# I2C.net
KiCad netlist of a schematic drawn in Altium Designer
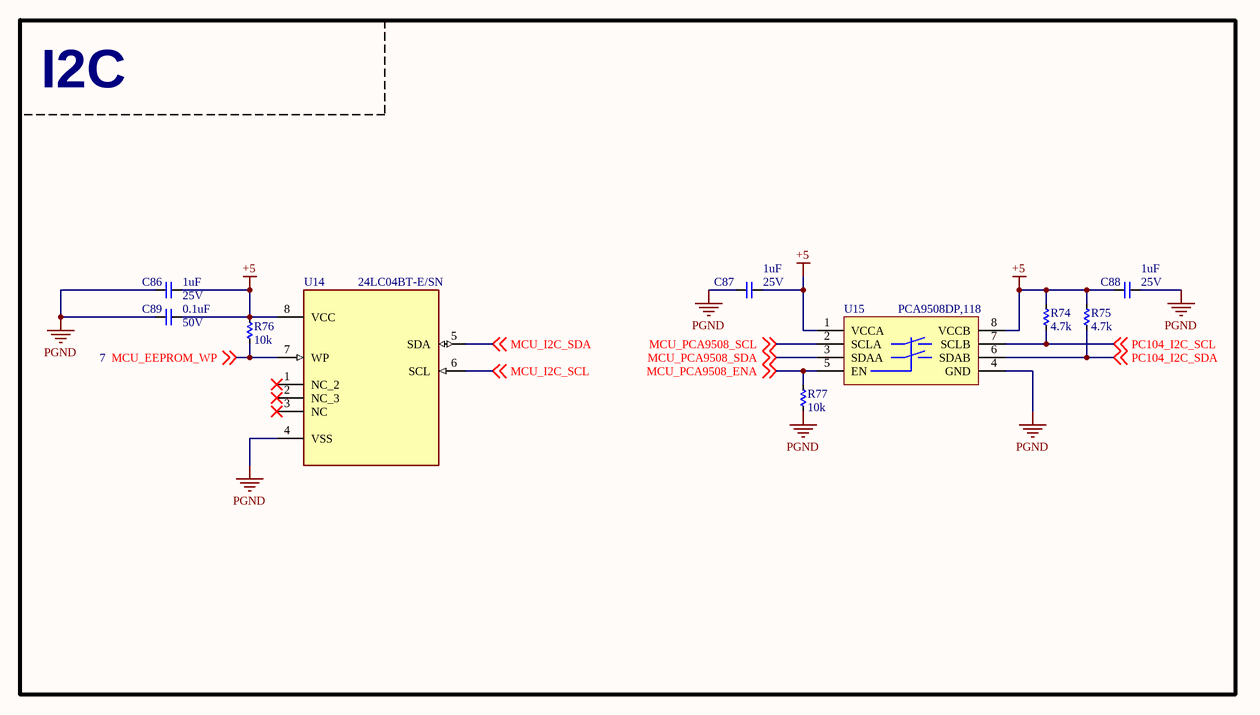
[diagram p0: I2C.SchDoc]

(export (version "E")
  (design (tool "Eeschema 10.0.6"))
  (components
    (comp (ref "C86")
      (value "1uF")
      (footprint "CAP_C_1608X80")
      (description "CAP")
      (fields (field (name "VOLTAGE") "25V"))
      (libsource (lib "LABLIB") (part "_CAP_C_2"))
    )
    (comp (ref "C87")
      (value "1uF")
      (footprint "CAP_C_1608X80")
      (description "CAP")
      (fields (field (name "VOLTAGE") "25V"))
      (libsource (lib "LABLIB") (part "_CAP_C_2"))
    )
    (comp (ref "C88")
      (value "1uF")
      (footprint "CAP_C_1608X80")
      (description "CAP")
      (fields (field (name "VOLTAGE") "25V"))
      (libsource (lib "LABLIB") (part "_CAP_C_2"))
    )
    (comp (ref "C89")
      (value "0.1uF")
      (footprint "CAP_C_1608X80")
      (description "CAP")
      (fields (field (name "VOLTAGE") "50V"))
      (libsource (lib "LABLIB") (part "_CAP_C_2"))
    )
    (comp (ref "R74")
      (value "4.7k")
      (footprint "RES_C_1608X60")
      (description "RES")
      (libsource (lib "LABLIB") (part "_RES_B_2_2"))
    )
    (comp (ref "R75")
      (value "4.7k")
      (footprint "RES_C_1608X60")
      (description "RES")
      (libsource (lib "LABLIB") (part "_RES_B_2_2"))
    )
    (comp (ref "R76")
      (value "10k")
      (footprint "RES_C_1608X60")
      (description "RES")
      (libsource (lib "LABLIB") (part "_RES_B_2_2"))
    )
    (comp (ref "R77")
      (value "10k")
      (footprint "RES_C_1608X60")
      (description "RES")
      (libsource (lib "LABLIB") (part "_RES_B_2_2"))
    )
    (comp (ref "U14")
      (value "24LC04BT-E/SN")
      (footprint "SOIC_127")
      (libsource (lib "KIENASIY123_LIB") (part "24LC04BT-E/SN"))
    )
    (comp (ref "U15")
      (value "PCA9508DP,118")
      (footprint "TSOP8")
      (libsource (lib "EXP_HW_V3") (part "PCA9508DP,118"))
    )
  )
  (nets
    (net (code "1") (name "+5") (class "Default")
      (node (ref "C86") (pin "1") (pinfunction "1_1") (pintype "passive"))
      (node (ref "C87") (pin "2") (pinfunction "2_2") (pintype "passive"))
      (node (ref "C88") (pin "2") (pinfunction "2_2") (pintype "passive"))
      (node (ref "C89") (pin "1") (pinfunction "1_1") (pintype "passive"))
      (node (ref "R74") (pin "1") (pinfunction "1_1") (pintype "passive"))
      (node (ref "R75") (pin "1") (pinfunction "1_1") (pintype "passive"))
      (node (ref "R76") (pin "1") (pinfunction "1_1") (pintype "passive"))
      (node (ref "U14") (pin "8") (pinfunction "VCC_8") (pintype "power_in"))
      (node (ref "U15") (pin "1") (pinfunction "VCCA_1") (pintype "passive"))
      (node (ref "U15") (pin "8") (pinfunction "VCCB_8") (pintype "passive"))
    )
    (net (code "2") (name "MCU_EEPROM_WP") (class "Default")
      (node (ref "R76") (pin "2") (pinfunction "2_2") (pintype "passive"))
      (node (ref "U14") (pin "7") (pinfunction "WP_7") (pintype "input"))
    )
    (net (code "3") (name "MCU_I2C_SCL") (class "Default")
      (node (ref "U14") (pin "6") (pinfunction "SCL_6") (pintype "input"))
    )
    (net (code "4") (name "MCU_I2C_SDA") (class "Default")
      (node (ref "U14") (pin "5") (pinfunction "SDA_5") (pintype "bidirectional"))
    )
    (net (code "5") (name "MCU_PCA9508_ENA") (class "Default")
      (node (ref "R77") (pin "2") (pinfunction "2_2") (pintype "passive"))
      (node (ref "U15") (pin "5") (pinfunction "EN_5") (pintype "passive"))
    )
    (net (code "6") (name "MCU_PCA9508_SCL") (class "Default")
      (node (ref "U15") (pin "2") (pinfunction "SCLA_2") (pintype "passive"))
    )
    (net (code "7") (name "MCU_PCA9508_SDA") (class "Default")
      (node (ref "U15") (pin "3") (pinfunction "SDAA_3") (pintype "passive"))
    )
    (net (code "8") (name "PC104_I2C_SCL") (class "Default")
      (node (ref "R74") (pin "2") (pinfunction "2_2") (pintype "passive"))
      (node (ref "U15") (pin "7") (pinfunction "SCLB_7") (pintype "passive"))
    )
    (net (code "9") (name "PC104_I2C_SDA") (class "Default")
      (node (ref "R75") (pin "2") (pinfunction "2_2") (pintype "passive"))
      (node (ref "U15") (pin "6") (pinfunction "SDAB_6") (pintype "passive"))
    )
    (net (code "10") (name "PGND") (class "Default")
      (node (ref "C86") (pin "2") (pinfunction "2_2") (pintype "passive"))
      (node (ref "C87") (pin "1") (pinfunction "1_1") (pintype "passive"))
      (node (ref "C88") (pin "1") (pinfunction "1_1") (pintype "passive"))
      (node (ref "C89") (pin "2") (pinfunction "2_2") (pintype "passive"))
      (node (ref "R77") (pin "1") (pinfunction "1_1") (pintype "passive"))
      (node (ref "U14") (pin "4") (pinfunction "VSS_4") (pintype "power_in"))
      (node (ref "U15") (pin "4") (pinfunction "GND_4") (pintype "passive"))
    )
    (net (code "11") (name "unconnected-(U14-NC-Pad3)") (class "Default")
      (node (ref "U14") (pin "3") (pinfunction "NC_3") (pintype "passive+no_connect"))
    )
    (net (code "12") (name "unconnected-(U14-NC_2-Pad1)") (class "Default")
      (node (ref "U14") (pin "1") (pinfunction "NC_2_1") (pintype "passive+no_connect"))
    )
    (net (code "13") (name "unconnected-(U14-NC_3-Pad2)") (class "Default")
      (node (ref "U14") (pin "2") (pinfunction "NC_3_2") (pintype "passive+no_connect"))
    )
  )
)
